# Proximity_Sensor.net
KiCad netlist of a schematic drawn in Altium Designer
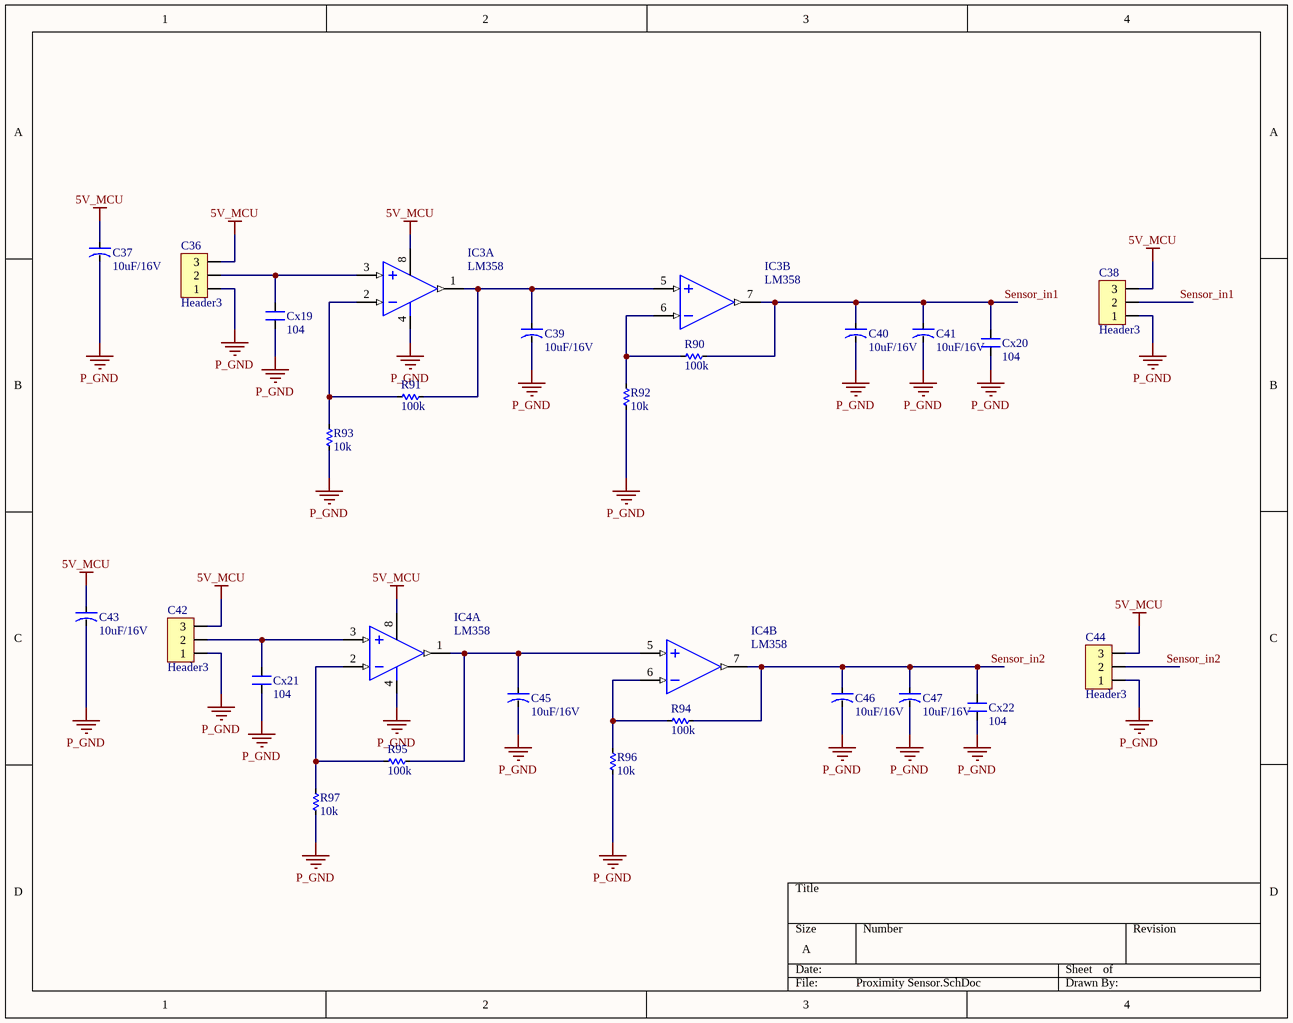
[diagram p0: Proximity Sensor.SchDoc]

(export (version "E")
  (design (tool "Eeschema 10.0.6"))
  (components
    (comp (ref "C36")
      (value "Header3")
      (footprint "Header3")
      (description "Header IDC, 3 x 1 Pin Vertical 2.54mm Pitch (Non-Boxed, Male)")
      (fields
        (field (name "MANUFACTURER") "Würth Elektronik eiSos GmbH")
        (field (name "PARTNO") "613002143121")
        (field (name "CREATED BY") "Karrer Zheng")
      )
      (libsource (lib "LIBRARY") (part "Header3"))
    )
    (comp (ref "C37")
      (value "10uF/16V")
      (footprint "TANTALUM-3216")
      (libsource (lib "LIBRARY") (part "CN-TANTALUM-SMD"))
    )
    (comp (ref "C38")
      (value "Header3")
      (footprint "Header3")
      (description "Header IDC, 3 x 1 Pin Vertical 2.54mm Pitch (Non-Boxed, Male)")
      (fields
        (field (name "MANUFACTURER") "Würth Elektronik eiSos GmbH")
        (field (name "PARTNO") "613002143121")
        (field (name "CREATED BY") "Karrer Zheng")
      )
      (libsource (lib "LIBRARY") (part "Header3"))
    )
    (comp (ref "C39")
      (value "10uF/16V")
      (footprint "TANTALUM-3216")
      (libsource (lib "LIBRARY") (part "CN-TANTALUM-SMD"))
    )
    (comp (ref "C40")
      (value "10uF/16V")
      (footprint "TANTALUM-3216")
      (libsource (lib "LIBRARY") (part "CN-TANTALUM-SMD"))
    )
    (comp (ref "C41")
      (value "10uF/16V")
      (footprint "TANTALUM-3216")
      (libsource (lib "LIBRARY") (part "CN-TANTALUM-SMD"))
    )
    (comp (ref "C42")
      (value "Header3")
      (footprint "Header3")
      (description "Header IDC, 3 x 1 Pin Vertical 2.54mm Pitch (Non-Boxed, Male)")
      (fields
        (field (name "MANUFACTURER") "Würth Elektronik eiSos GmbH")
        (field (name "PARTNO") "613002143121")
        (field (name "CREATED BY") "Karrer Zheng")
      )
      (libsource (lib "LIBRARY") (part "Header3"))
    )
    (comp (ref "C43")
      (value "10uF/16V")
      (footprint "TANTALUM-3216")
      (libsource (lib "LIBRARY") (part "CN-TANTALUM-SMD"))
    )
    (comp (ref "C44")
      (value "Header3")
      (footprint "Header3")
      (description "Header IDC, 3 x 1 Pin Vertical 2.54mm Pitch (Non-Boxed, Male)")
      (fields
        (field (name "MANUFACTURER") "Würth Elektronik eiSos GmbH")
        (field (name "PARTNO") "613002143121")
        (field (name "CREATED BY") "Karrer Zheng")
      )
      (libsource (lib "LIBRARY") (part "Header3"))
    )
    (comp (ref "C45")
      (value "10uF/16V")
      (footprint "TANTALUM-3216")
      (libsource (lib "LIBRARY") (part "CN-TANTALUM-SMD"))
    )
    (comp (ref "C46")
      (value "10uF/16V")
      (footprint "TANTALUM-3216")
      (libsource (lib "LIBRARY") (part "CN-TANTALUM-SMD"))
    )
    (comp (ref "C47")
      (value "10uF/16V")
      (footprint "TANTALUM-3216")
      (libsource (lib "LIBRARY") (part "CN-TANTALUM-SMD"))
    )
    (comp (ref "Cx19") (value "104") (footprint "CN-SMD-0805") (libsource (lib "LIBRARY") (part "CN")))
    (comp (ref "Cx20") (value "104") (footprint "CN-SMD-0805") (libsource (lib "LIBRARY") (part "CN")))
    (comp (ref "Cx21") (value "104") (footprint "CN-SMD-0805") (libsource (lib "LIBRARY") (part "CN")))
    (comp (ref "Cx22") (value "104") (footprint "CN-SMD-0805") (libsource (lib "LIBRARY") (part "CN")))
    (comp (ref "IC3")
      (value "LM358")
      (footprint "SO8")
      (description "Low-Power Dual Operational Amplifier")
      (libsource (lib "LIBRARY") (part "LM358"))
    )
    (comp (ref "IC4")
      (value "LM358")
      (footprint "SO8")
      (description "Low-Power Dual Operational Amplifier")
      (libsource (lib "LIBRARY") (part "LM358"))
    )
    (comp (ref "R90")
      (value "100k")
      (footprint "RES-SMD-0805")
      (description "Resistor")
      (fields
        (field (name "MANUFACTURER") "Generic Components")
        (field (name "PUBLISHER") "Altium Hobart Technology Centre")
      )
      (libsource (lib "LIBRARY") (part "Res-SMD"))
    )
    (comp (ref "R91")
      (value "100k")
      (footprint "RES-SMD-0805")
      (description "Resistor")
      (fields
        (field (name "MANUFACTURER") "Generic Components")
        (field (name "PUBLISHER") "Altium Hobart Technology Centre")
      )
      (libsource (lib "LIBRARY") (part "Res-SMD"))
    )
    (comp (ref "R92")
      (value "10k")
      (footprint "RES-SMD-0805")
      (description "Resistor")
      (fields
        (field (name "MANUFACTURER") "Generic Components")
        (field (name "PUBLISHER") "Altium Hobart Technology Centre")
      )
      (libsource (lib "LIBRARY") (part "Res-SMD"))
    )
    (comp (ref "R93")
      (value "10k")
      (footprint "RES-SMD-0805")
      (description "Resistor")
      (fields
        (field (name "MANUFACTURER") "Generic Components")
        (field (name "PUBLISHER") "Altium Hobart Technology Centre")
      )
      (libsource (lib "LIBRARY") (part "Res-SMD"))
    )
    (comp (ref "R94")
      (value "100k")
      (footprint "RES-SMD-0805")
      (description "Resistor")
      (fields
        (field (name "MANUFACTURER") "Generic Components")
        (field (name "PUBLISHER") "Altium Hobart Technology Centre")
      )
      (libsource (lib "LIBRARY") (part "Res-SMD"))
    )
    (comp (ref "R95")
      (value "100k")
      (footprint "RES-SMD-0805")
      (description "Resistor")
      (fields
        (field (name "MANUFACTURER") "Generic Components")
        (field (name "PUBLISHER") "Altium Hobart Technology Centre")
      )
      (libsource (lib "LIBRARY") (part "Res-SMD"))
    )
    (comp (ref "R96")
      (value "10k")
      (footprint "RES-SMD-0805")
      (description "Resistor")
      (fields
        (field (name "MANUFACTURER") "Generic Components")
        (field (name "PUBLISHER") "Altium Hobart Technology Centre")
      )
      (libsource (lib "LIBRARY") (part "Res-SMD"))
    )
    (comp (ref "R97")
      (value "10k")
      (footprint "RES-SMD-0805")
      (description "Resistor")
      (fields
        (field (name "MANUFACTURER") "Generic Components")
        (field (name "PUBLISHER") "Altium Hobart Technology Centre")
      )
      (libsource (lib "LIBRARY") (part "Res-SMD"))
    )
  )
  (nets
    (net (code "1") (name "/Sensor_in1") (class "Default")
      (node (ref "C38") (pin "2") (pinfunction "2_2") (pintype "passive"))
      (node (ref "C40") (pin "1") (pinfunction "1_1") (pintype "passive"))
      (node (ref "C41") (pin "1") (pinfunction "1_1") (pintype "passive"))
      (node (ref "Cx20") (pin "2") (pinfunction "2_2") (pintype "passive"))
      (node (ref "IC3") (pin "7") (pinfunction "OUT_7") (pintype "output"))
      (node (ref "R90") (pin "1") (pinfunction "1_1") (pintype "passive"))
    )
    (net (code "2") (name "/Sensor_in2") (class "Default")
      (node (ref "C44") (pin "2") (pinfunction "2_2") (pintype "passive"))
      (node (ref "C46") (pin "1") (pinfunction "1_1") (pintype "passive"))
      (node (ref "C47") (pin "1") (pinfunction "1_1") (pintype "passive"))
      (node (ref "Cx22") (pin "2") (pinfunction "2_2") (pintype "passive"))
      (node (ref "IC4") (pin "7") (pinfunction "OUT_7") (pintype "output"))
      (node (ref "R94") (pin "1") (pinfunction "1_1") (pintype "passive"))
    )
    (net (code "3") (name "5V_MCU") (class "Default")
      (node (ref "C36") (pin "3") (pinfunction "3_3") (pintype "passive"))
      (node (ref "C37") (pin "1") (pinfunction "1_1") (pintype "passive"))
      (node (ref "C38") (pin "3") (pinfunction "3_3") (pintype "passive"))
      (node (ref "C42") (pin "3") (pinfunction "3_3") (pintype "passive"))
      (node (ref "C43") (pin "1") (pinfunction "1_1") (pintype "passive"))
      (node (ref "C44") (pin "3") (pinfunction "3_3") (pintype "passive"))
      (node (ref "IC3") (pin "8") (pinfunction "+V_8") (pintype "passive"))
      (node (ref "IC4") (pin "8") (pinfunction "+V_8") (pintype "passive"))
    )
    (net (code "4") (name "Net-(IC3A-IN+)") (class "Default")
      (node (ref "C36") (pin "2") (pinfunction "2_2") (pintype "passive"))
      (node (ref "Cx19") (pin "2") (pinfunction "2_2") (pintype "passive"))
      (node (ref "IC3") (pin "3") (pinfunction "IN+_3") (pintype "input"))
    )
    (net (code "5") (name "Net-(IC3A-IN-)") (class "Default")
      (node (ref "IC3") (pin "2") (pinfunction "IN-_2") (pintype "input"))
      (node (ref "R91") (pin "2") (pinfunction "2_2") (pintype "passive"))
      (node (ref "R93") (pin "1") (pinfunction "1_1") (pintype "passive"))
    )
    (net (code "6") (name "Net-(IC3A-OUT)") (class "Default")
      (node (ref "C39") (pin "1") (pinfunction "1_1") (pintype "passive"))
      (node (ref "IC3") (pin "1") (pinfunction "OUT_1") (pintype "output"))
      (node (ref "IC3") (pin "5") (pinfunction "IN+_5") (pintype "input"))
      (node (ref "R91") (pin "1") (pinfunction "1_1") (pintype "passive"))
    )
    (net (code "7") (name "Net-(IC3B-IN-)") (class "Default")
      (node (ref "IC3") (pin "6") (pinfunction "IN-_6") (pintype "input"))
      (node (ref "R90") (pin "2") (pinfunction "2_2") (pintype "passive"))
      (node (ref "R92") (pin "1") (pinfunction "1_1") (pintype "passive"))
    )
    (net (code "8") (name "Net-(IC4A-IN+)") (class "Default")
      (node (ref "C42") (pin "2") (pinfunction "2_2") (pintype "passive"))
      (node (ref "Cx21") (pin "2") (pinfunction "2_2") (pintype "passive"))
      (node (ref "IC4") (pin "3") (pinfunction "IN+_3") (pintype "input"))
    )
    (net (code "9") (name "Net-(IC4A-IN-)") (class "Default")
      (node (ref "IC4") (pin "2") (pinfunction "IN-_2") (pintype "input"))
      (node (ref "R95") (pin "2") (pinfunction "2_2") (pintype "passive"))
      (node (ref "R97") (pin "1") (pinfunction "1_1") (pintype "passive"))
    )
    (net (code "10") (name "Net-(IC4A-OUT)") (class "Default")
      (node (ref "C45") (pin "1") (pinfunction "1_1") (pintype "passive"))
      (node (ref "IC4") (pin "1") (pinfunction "OUT_1") (pintype "output"))
      (node (ref "IC4") (pin "5") (pinfunction "IN+_5") (pintype "input"))
      (node (ref "R95") (pin "1") (pinfunction "1_1") (pintype "passive"))
    )
    (net (code "11") (name "Net-(IC4B-IN-)") (class "Default")
      (node (ref "IC4") (pin "6") (pinfunction "IN-_6") (pintype "input"))
      (node (ref "R94") (pin "2") (pinfunction "2_2") (pintype "passive"))
      (node (ref "R96") (pin "1") (pinfunction "1_1") (pintype "passive"))
    )
    (net (code "12") (name "P_GND") (class "Default")
      (node (ref "C36") (pin "1") (pinfunction "1_1") (pintype "passive"))
      (node (ref "C37") (pin "2") (pinfunction "2_2") (pintype "passive"))
      (node (ref "C38") (pin "1") (pinfunction "1_1") (pintype "passive"))
      (node (ref "C39") (pin "2") (pinfunction "2_2") (pintype "passive"))
      (node (ref "C40") (pin "2") (pinfunction "2_2") (pintype "passive"))
      (node (ref "C41") (pin "2") (pinfunction "2_2") (pintype "passive"))
      (node (ref "C42") (pin "1") (pinfunction "1_1") (pintype "passive"))
      (node (ref "C43") (pin "2") (pinfunction "2_2") (pintype "passive"))
      (node (ref "C44") (pin "1") (pinfunction "1_1") (pintype "passive"))
      (node (ref "C45") (pin "2") (pinfunction "2_2") (pintype "passive"))
      (node (ref "C46") (pin "2") (pinfunction "2_2") (pintype "passive"))
      (node (ref "C47") (pin "2") (pinfunction "2_2") (pintype "passive"))
      (node (ref "Cx19") (pin "1") (pinfunction "1_1") (pintype "passive"))
      (node (ref "Cx20") (pin "1") (pinfunction "1_1") (pintype "passive"))
      (node (ref "Cx21") (pin "1") (pinfunction "1_1") (pintype "passive"))
      (node (ref "Cx22") (pin "1") (pinfunction "1_1") (pintype "passive"))
      (node (ref "IC3") (pin "4") (pinfunction "-V_4") (pintype "passive"))
      (node (ref "IC4") (pin "4") (pinfunction "-V_4") (pintype "passive"))
      (node (ref "R92") (pin "2") (pinfunction "2_2") (pintype "passive"))
      (node (ref "R93") (pin "2") (pinfunction "2_2") (pintype "passive"))
      (node (ref "R96") (pin "2") (pinfunction "2_2") (pintype "passive"))
      (node (ref "R97") (pin "2") (pinfunction "2_2") (pintype "passive"))
    )
  )
)
